# trackoon_solar.net
KiCad netlist of a schematic drawn in EAGLE
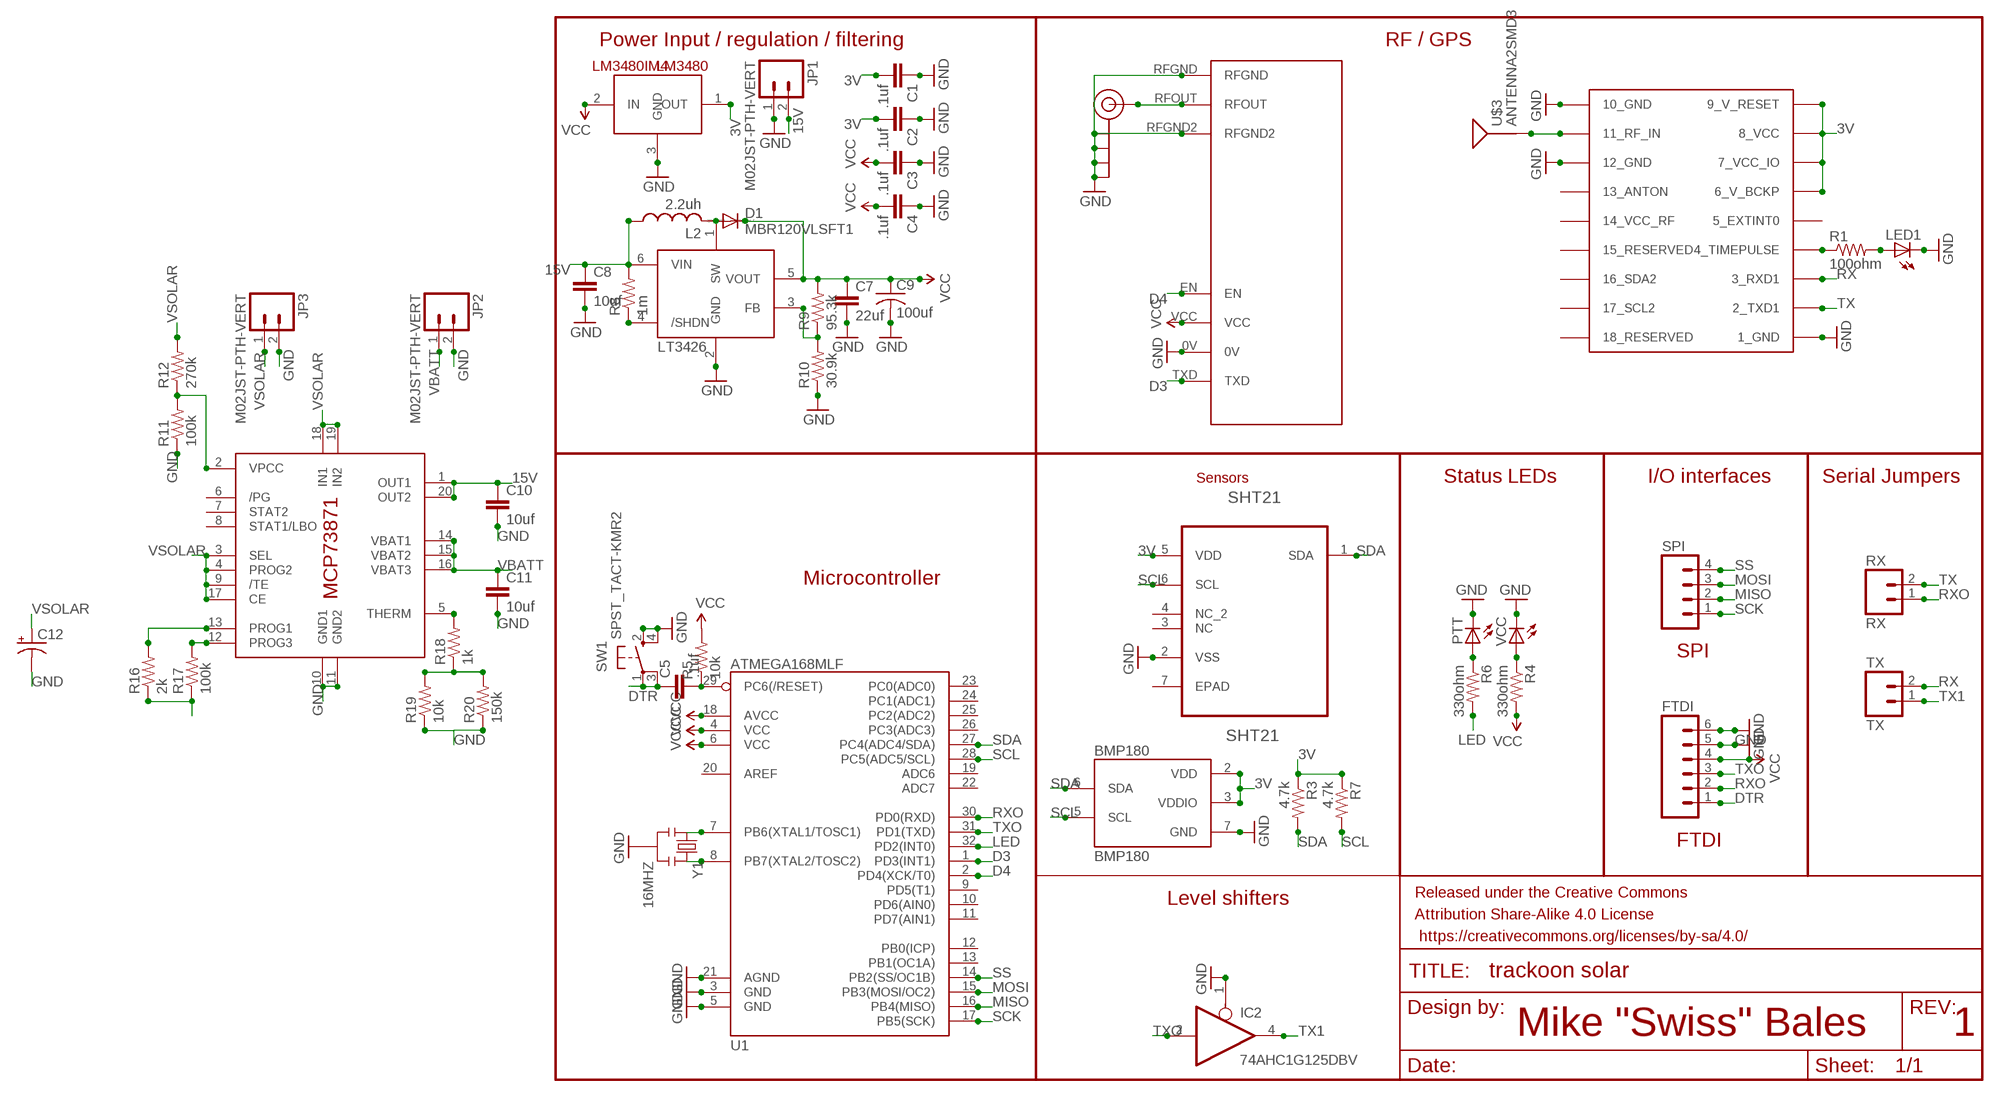
[diagram p0: schematic, sheet 1]

(export (version "E")
  (design (tool "Eeschema 10.0.6"))
  (components
    (comp (ref "BMP180")
      (value "BMP180")
      (footprint "eagle-import:BMP180")
      (libsource (lib "eagle-import") (part "BMP180"))
    )
    (comp (ref "C1")
      (value ".1uf")
      (footprint "eagle-import:0805")
      (libsource (lib "eagle-import") (part "CAP0805"))
    )
    (comp (ref "C2")
      (value ".1uf")
      (footprint "eagle-import:0805")
      (libsource (lib "eagle-import") (part "CAP0805"))
    )
    (comp (ref "C3")
      (value ".1uf")
      (footprint "eagle-import:0805")
      (libsource (lib "eagle-import") (part "CAP0805"))
    )
    (comp (ref "C4")
      (value ".1uf")
      (footprint "eagle-import:0805")
      (libsource (lib "eagle-import") (part "CAP0805"))
    )
    (comp (ref "C5")
      (value ".1uf")
      (footprint "eagle-import:0805")
      (libsource (lib "eagle-import") (part "CAP0805"))
    )
    (comp (ref "C7")
      (value "22uf")
      (footprint "eagle-import:0805")
      (libsource (lib "eagle-import") (part "CAP0805"))
    )
    (comp (ref "C8")
      (value "10uf")
      (footprint "eagle-import:0805")
      (libsource (lib "eagle-import") (part "CAP0805"))
    )
    (comp (ref "C9")
      (value "100uf")
      (footprint "eagle-import:C1206")
      (libsource (lib "eagle-import") (part "C-USC1206"))
    )
    (comp (ref "C10")
      (value "10uf")
      (footprint "eagle-import:0805")
      (libsource (lib "eagle-import") (part "CAP0805"))
    )
    (comp (ref "C11")
      (value "10uf")
      (footprint "eagle-import:0805")
      (libsource (lib "eagle-import") (part "CAP0805"))
    )
    (comp (ref "C12")
      (value "CPOL-US153CLV-1012")
      (footprint "eagle-import:153CLV-1012")
      (libsource (lib "eagle-import") (part "CPOL-US153CLV-1012"))
    )
    (comp (ref "D1")
      (value "MBR120VLSFT1")
      (footprint "eagle-import:SOD123")
      (libsource (lib "eagle-import") (part "DIODE-SOD123"))
    )
    (comp (ref "FRAME1")
      (value "FRAME-LETTER")
      (footprint "eagle-import:CREATIVE_COMMONS")
      (libsource (lib "eagle-import") (part "FRAME-LETTER"))
    )
    (comp (ref "FTDI")
      (value "M06NO_SILK_FEMALE_PTH")
      (footprint "eagle-import:1X06_NO_SILK")
      (libsource (lib "eagle-import") (part "M06NO_SILK_FEMALE_PTH"))
    )
    (comp (ref "IC1")
      (value "MCP73871")
      (footprint "eagle-import:QFN20")
      (libsource (lib "eagle-import") (part "MCP73871"))
    )
    (comp (ref "IC2")
      (value "74AHC1G125DBV")
      (footprint "eagle-import:SOT23-5")
      (libsource (lib "eagle-import") (part "741G125DBVAHC"))
    )
    (comp (ref "J$1")
      (value "SMA_EDGE")
      (footprint "eagle-import:SMA-EDGE")
      (libsource (lib "eagle-import") (part "SMA_EDGE"))
    )
    (comp (ref "JP1")
      (value "M02JST-PTH-VERT")
      (footprint "eagle-import:JST-2-PTH-VERT")
      (libsource (lib "eagle-import") (part "M02JST-PTH-VERT"))
    )
    (comp (ref "JP2")
      (value "M02JST-PTH-VERT")
      (footprint "eagle-import:JST-2-PTH-VERT")
      (libsource (lib "eagle-import") (part "M02JST-PTH-VERT"))
    )
    (comp (ref "JP3")
      (value "M02JST-PTH-VERT")
      (footprint "eagle-import:JST-2-PTH-VERT")
      (libsource (lib "eagle-import") (part "M02JST-PTH-VERT"))
    )
    (comp (ref "L2")
      (value "2.2uh")
      (footprint "eagle-import:L1812")
      (libsource (lib "eagle-import") (part "L-USL1812"))
    )
    (comp (ref "LED1")
      (value "LEDCHIP-LED0805")
      (footprint "eagle-import:CHIP-LED0805")
      (libsource (lib "eagle-import") (part "LEDCHIP-LED0805"))
    )
    (comp (ref "LM3480")
      (value "LM3480IM4")
      (footprint "eagle-import:SOT23-3")
      (libsource (lib "eagle-import") (part "LM3480IM4"))
    )
    (comp (ref "LT3426")
      (value "LT3426")
      (footprint "eagle-import:SOT23-6")
      (libsource (lib "eagle-import") (part "LT3426"))
    )
    (comp (ref "PTT")
      (value "LEDCHIP-LED0805")
      (footprint "eagle-import:CHIP-LED0805")
      (libsource (lib "eagle-import") (part "LEDCHIP-LED0805"))
    )
    (comp (ref "R1")
      (value "100ohm")
      (footprint "eagle-import:0805")
      (libsource (lib "eagle-import") (part "RESISTOR0805-RES"))
    )
    (comp (ref "R3")
      (value "4.7k")
      (footprint "eagle-import:0805")
      (libsource (lib "eagle-import") (part "RESISTOR0805-RES"))
    )
    (comp (ref "R4")
      (value "330ohm")
      (footprint "eagle-import:0805")
      (libsource (lib "eagle-import") (part "RESISTOR0805-RES"))
    )
    (comp (ref "R5")
      (value "10k")
      (footprint "eagle-import:0805")
      (libsource (lib "eagle-import") (part "RESISTOR0805-RES"))
    )
    (comp (ref "R6")
      (value "330ohm")
      (footprint "eagle-import:0805")
      (libsource (lib "eagle-import") (part "RESISTOR0805-RES"))
    )
    (comp (ref "R7")
      (value "4.7k")
      (footprint "eagle-import:0805")
      (libsource (lib "eagle-import") (part "RESISTOR0805-RES"))
    )
    (comp (ref "R8")
      (value "1m")
      (footprint "eagle-import:0805")
      (libsource (lib "eagle-import") (part "RESISTOR0805-RES"))
    )
    (comp (ref "R9")
      (value "95.3k")
      (footprint "eagle-import:0805")
      (libsource (lib "eagle-import") (part "RESISTOR0805-RES"))
    )
    (comp (ref "R10")
      (value "30.9k")
      (footprint "eagle-import:0805")
      (libsource (lib "eagle-import") (part "RESISTOR0805-RES"))
    )
    (comp (ref "R11")
      (value "100k")
      (footprint "eagle-import:0805")
      (libsource (lib "eagle-import") (part "RESISTOR0805-RES"))
    )
    (comp (ref "R12")
      (value "270k")
      (footprint "eagle-import:0805")
      (libsource (lib "eagle-import") (part "RESISTOR0805-RES"))
    )
    (comp (ref "R16")
      (value "2k")
      (footprint "eagle-import:0805")
      (libsource (lib "eagle-import") (part "RESISTOR0805-RES"))
    )
    (comp (ref "R17")
      (value "100k")
      (footprint "eagle-import:0805")
      (libsource (lib "eagle-import") (part "RESISTOR0805-RES"))
    )
    (comp (ref "R18")
      (value "1k")
      (footprint "eagle-import:0805")
      (libsource (lib "eagle-import") (part "RESISTOR0805-RES"))
    )
    (comp (ref "R19")
      (value "10k")
      (footprint "eagle-import:0805")
      (libsource (lib "eagle-import") (part "RESISTOR0805-RES"))
    )
    (comp (ref "R20")
      (value "150k")
      (footprint "eagle-import:0805")
      (libsource (lib "eagle-import") (part "RESISTOR0805-RES"))
    )
    (comp (ref "RX")
      (value "RX")
      (footprint "eagle-import:1X02")
      (libsource (lib "eagle-import") (part "M02PTH"))
    )
    (comp (ref "SHT21")
      (value "SHT21")
      (footprint "eagle-import:DFN300X300X110-7N")
      (libsource (lib "eagle-import") (part "SHT21"))
    )
    (comp (ref "SPI")
      (value "M041X04_NO_SILK")
      (footprint "eagle-import:1X04_NO_SILK")
      (libsource (lib "eagle-import") (part "M041X04_NO_SILK"))
    )
    (comp (ref "SW1")
      (value "SPST_TACT-KMR2")
      (footprint "eagle-import:KMR2")
      (libsource (lib "eagle-import") (part "SPST_TACT-KMR2"))
    )
    (comp (ref "TX")
      (value "TX")
      (footprint "eagle-import:1X02")
      (libsource (lib "eagle-import") (part "M02PTH"))
    )
    (comp (ref "U$1")
      (value "UBLOX_MAX")
      (footprint "eagle-import:UBLOX_MAX")
      (libsource (lib "eagle-import") (part "UBLOX_MAX"))
    )
    (comp (ref "U$2")
      (value "RADIOMETRIX-HX1")
      (footprint "eagle-import:RADIOMETRIX-HX1")
      (libsource (lib "eagle-import") (part "RADIOMETRIX-HX1"))
    )
    (comp (ref "U$3")
      (value "ANTENNA2SMD3")
      (footprint "eagle-import:ANTENNA-CHIP4")
      (libsource (lib "eagle-import") (part "ANTENNA2SMD3"))
    )
    (comp (ref "U1")
      (value "ATMEGA168MLF")
      (footprint "eagle-import:MLF32")
      (libsource (lib "eagle-import") (part "ATMEGA168MLF"))
    )
    (comp (ref "VCC")
      (value "LEDCHIP-LED0805")
      (footprint "eagle-import:CHIP-LED0805")
      (libsource (lib "eagle-import") (part "LEDCHIP-LED0805"))
    )
    (comp (ref "Y1")
      (value "16MHZ")
      (footprint "eagle-import:RESONATOR-SMD")
      (libsource (lib "eagle-import") (part "RESONATOR16MHZ"))
    )
  )
  (nets
    (net (code "1") (name "/3V") (class "Default")
      (node (ref "BMP180") (pin "2") (pinfunction "VDD_2") (pintype "power_in"))
      (node (ref "BMP180") (pin "3") (pinfunction "VDDIO_3") (pintype "power_in"))
      (node (ref "C1") (pin "2") (pinfunction "2_2") (pintype "passive"))
      (node (ref "C2") (pin "2") (pinfunction "2_2") (pintype "passive"))
      (node (ref "LM3480") (pin "1") (pinfunction "OUT_1") (pintype "bidirectional"))
      (node (ref "R3") (pin "1") (pinfunction "1_1") (pintype "passive"))
      (node (ref "R7") (pin "1") (pinfunction "1_1") (pintype "passive"))
      (node (ref "SHT21") (pin "5") (pinfunction "VDD_5") (pintype "power_in"))
      (node (ref "U$1") (pin "6_V_BCKP") (pinfunction "6_V_BCKP_6_V_BCKP") (pintype "bidirectional"))
      (node (ref "U$1") (pin "7_VCC_IO") (pinfunction "7_VCC_IO_7_VCC_IO") (pintype "power_in"))
      (node (ref "U$1") (pin "8_VCC") (pinfunction "8_VCC_8_VCC") (pintype "power_in"))
      (node (ref "U$1") (pin "9_V_RESET") (pinfunction "9_V_RESET_9_V_RESET") (pintype "power_in"))
    )
    (net (code "2") (name "/15V") (class "Default")
      (node (ref "C10") (pin "1") (pinfunction "1_1") (pintype "passive"))
      (node (ref "C8") (pin "1") (pinfunction "1_1") (pintype "passive"))
      (node (ref "IC1") (pin "1") (pinfunction "OUT1_1") (pintype "output"))
      (node (ref "IC1") (pin "20") (pinfunction "OUT2_20") (pintype "output"))
      (node (ref "JP1") (pin "2") (pinfunction "2_2") (pintype "passive"))
      (node (ref "L2") (pin "1") (pinfunction "1_1") (pintype "passive"))
      (node (ref "LT3426") (pin "6") (pinfunction "VIN_6") (pintype "input"))
      (node (ref "R8") (pin "2") (pinfunction "2_2") (pintype "passive"))
    )
    (net (code "3") (name "/D3") (class "Default")
      (node (ref "U$2") (pin "TXD") (pinfunction "TXD_TXD") (pintype "bidirectional"))
      (node (ref "U1") (pin "1") (pinfunction "PD3(INT1)_1") (pintype "bidirectional"))
    )
    (net (code "4") (name "/D4") (class "Default")
      (node (ref "U$2") (pin "EN") (pinfunction "EN_EN") (pintype "bidirectional"))
      (node (ref "U1") (pin "2") (pinfunction "PD4(XCK/T0)_2") (pintype "bidirectional"))
    )
    (net (code "5") (name "/DTR") (class "Default")
      (node (ref "C5") (pin "1") (pinfunction "1_1") (pintype "passive"))
      (node (ref "FTDI") (pin "1") (pinfunction "1_1") (pintype "passive"))
      (node (ref "SW1") (pin "1") (pinfunction "P_1") (pintype "passive"))
      (node (ref "SW1") (pin "3") (pinfunction "P1_3") (pintype "passive"))
    )
    (net (code "6") (name "/LED") (class "Default")
      (node (ref "R6") (pin "2") (pinfunction "2_2") (pintype "passive"))
      (node (ref "U1") (pin "32") (pinfunction "PD2(INT0)_32") (pintype "bidirectional"))
    )
    (net (code "7") (name "/MISO") (class "Default")
      (node (ref "SPI") (pin "2") (pinfunction "2_2") (pintype "passive"))
      (node (ref "U1") (pin "16") (pinfunction "PB4(MISO)_16") (pintype "bidirectional"))
    )
    (net (code "8") (name "/MOSI") (class "Default")
      (node (ref "SPI") (pin "3") (pinfunction "3_3") (pintype "passive"))
      (node (ref "U1") (pin "15") (pinfunction "PB3(MOSI/OC2)_15") (pintype "bidirectional"))
    )
    (net (code "9") (name "/RX") (class "Default")
      (node (ref "TX") (pin "2") (pinfunction "2_2") (pintype "passive"))
      (node (ref "U$1") (pin "3_RXD1") (pinfunction "3_RXD1_3_RXD1") (pintype "bidirectional"))
    )
    (net (code "10") (name "/RXO") (class "Default")
      (node (ref "FTDI") (pin "2") (pinfunction "2_2") (pintype "passive"))
      (node (ref "RX") (pin "1") (pinfunction "1_1") (pintype "passive"))
      (node (ref "U1") (pin "30") (pinfunction "PD0(RXD)_30") (pintype "bidirectional"))
    )
    (net (code "11") (name "/SCK") (class "Default")
      (node (ref "SPI") (pin "1") (pinfunction "1_1") (pintype "passive"))
      (node (ref "U1") (pin "17") (pinfunction "PB5(SCK)_17") (pintype "bidirectional"))
    )
    (net (code "12") (name "/SCL") (class "Default")
      (node (ref "BMP180") (pin "5") (pinfunction "SCL_5") (pintype "input"))
      (node (ref "R7") (pin "2") (pinfunction "2_2") (pintype "passive"))
      (node (ref "SHT21") (pin "6") (pinfunction "SCL_6") (pintype "input"))
      (node (ref "U1") (pin "28") (pinfunction "PC5(ADC5/SCL)_28") (pintype "bidirectional"))
    )
    (net (code "13") (name "/SDA") (class "Default")
      (node (ref "BMP180") (pin "6") (pinfunction "SDA_6") (pintype "bidirectional"))
      (node (ref "R3") (pin "2") (pinfunction "2_2") (pintype "passive"))
      (node (ref "SHT21") (pin "1") (pinfunction "SDA_1") (pintype "bidirectional"))
      (node (ref "U1") (pin "27") (pinfunction "PC4(ADC4/SDA)_27") (pintype "bidirectional"))
    )
    (net (code "14") (name "/SS") (class "Default")
      (node (ref "SPI") (pin "4") (pinfunction "4_4") (pintype "passive"))
      (node (ref "U1") (pin "14") (pinfunction "PB2(SS/OC1B)_14") (pintype "bidirectional"))
    )
    (net (code "15") (name "/TX") (class "Default")
      (node (ref "RX") (pin "2") (pinfunction "2_2") (pintype "passive"))
      (node (ref "U$1") (pin "2_TXD1") (pinfunction "2_TXD1_2_TXD1") (pintype "bidirectional"))
    )
    (net (code "16") (name "/TX1") (class "Default")
      (node (ref "IC2") (pin "4") (pinfunction "O_4") (pintype "tri_state"))
      (node (ref "TX") (pin "1") (pinfunction "1_1") (pintype "passive"))
    )
    (net (code "17") (name "/TXO") (class "Default")
      (node (ref "FTDI") (pin "3") (pinfunction "3_3") (pintype "passive"))
      (node (ref "IC2") (pin "2") (pinfunction "I_2") (pintype "input"))
      (node (ref "U1") (pin "31") (pinfunction "PD1(TXD)_31") (pintype "bidirectional"))
    )
    (net (code "18") (name "/VBATT") (class "Default")
      (node (ref "C11") (pin "1") (pinfunction "1_1") (pintype "passive"))
      (node (ref "IC1") (pin "14") (pinfunction "VBAT1_14") (pintype "output"))
      (node (ref "IC1") (pin "15") (pinfunction "VBAT2_15") (pintype "output"))
      (node (ref "IC1") (pin "16") (pinfunction "VBAT3_16") (pintype "output"))
      (node (ref "JP2") (pin "1") (pinfunction "1_1") (pintype "passive"))
    )
    (net (code "19") (name "/VSOLAR") (class "Default")
      (node (ref "C12") (pin "+") (pinfunction "+_+") (pintype "passive"))
      (node (ref "IC1") (pin "17") (pinfunction "CE_17") (pintype "input"))
      (node (ref "IC1") (pin "18") (pinfunction "IN1_18") (pintype "input"))
      (node (ref "IC1") (pin "19") (pinfunction "IN2_19") (pintype "input"))
      (node (ref "IC1") (pin "3") (pinfunction "SEL_3") (pintype "input"))
      (node (ref "IC1") (pin "4") (pinfunction "PROG2_4") (pintype "input"))
      (node (ref "IC1") (pin "9") (pinfunction "/TE_9") (pintype "input"))
      (node (ref "JP3") (pin "1") (pinfunction "1_1") (pintype "passive"))
      (node (ref "R12") (pin "2") (pinfunction "2_2") (pintype "passive"))
    )
    (net (code "20") (name "GND") (class "Default")
      (node (ref "BMP180") (pin "7") (pinfunction "GND_7") (pintype "power_in"))
      (node (ref "C1") (pin "1") (pinfunction "1_1") (pintype "passive"))
      (node (ref "C10") (pin "2") (pinfunction "2_2") (pintype "passive"))
      (node (ref "C11") (pin "2") (pinfunction "2_2") (pintype "passive"))
      (node (ref "C12") (pin "-") (pinfunction "-_-") (pintype "passive"))
      (node (ref "C2") (pin "1") (pinfunction "1_1") (pintype "passive"))
      (node (ref "C3") (pin "1") (pinfunction "1_1") (pintype "passive"))
      (node (ref "C4") (pin "1") (pinfunction "1_1") (pintype "passive"))
      (node (ref "C7") (pin "2") (pinfunction "2_2") (pintype "passive"))
      (node (ref "C8") (pin "2") (pinfunction "2_2") (pintype "passive"))
      (node (ref "C9") (pin "2") (pinfunction "2_2") (pintype "passive"))
      (node (ref "FTDI") (pin "5") (pinfunction "5_5") (pintype "passive"))
      (node (ref "FTDI") (pin "6") (pinfunction "6_6") (pintype "passive"))
      (node (ref "IC1") (pin "10") (pinfunction "GND1_10") (pintype "power_in"))
      (node (ref "IC1") (pin "11") (pinfunction "GND2_11") (pintype "power_in"))
      (node (ref "IC2") (pin "1") (pinfunction "OE_1") (pintype "input"))
      (node (ref "J$1") (pin "GND@0") (pinfunction "GND_GND@0") (pintype "bidirectional"))
      (node (ref "J$1") (pin "GND@1") (pinfunction "GND_GND@1") (pintype "bidirectional"))
      (node (ref "J$1") (pin "GND@2") (pinfunction "GND_GND@2") (pintype "bidirectional"))
      (node (ref "J$1") (pin "GND@3") (pinfunction "GND_GND@3") (pintype "bidirectional"))
      (node (ref "JP1") (pin "1") (pinfunction "1_1") (pintype "passive"))
      (node (ref "JP2") (pin "2") (pinfunction "2_2") (pintype "passive"))
      (node (ref "JP3") (pin "2") (pinfunction "2_2") (pintype "passive"))
      (node (ref "LED1") (pin "C") (pinfunction "C_C") (pintype "passive"))
      (node (ref "LM3480") (pin "3") (pinfunction "GND_3") (pintype "bidirectional"))
      (node (ref "LT3426") (pin "2") (pinfunction "GND_2") (pintype "power_in"))
      (node (ref "PTT") (pin "C") (pinfunction "C_C") (pintype "passive"))
      (node (ref "R10") (pin "1") (pinfunction "1_1") (pintype "passive"))
      (node (ref "R11") (pin "1") (pinfunction "1_1") (pintype "passive"))
      (node (ref "R16") (pin "1") (pinfunction "1_1") (pintype "passive"))
      (node (ref "R17") (pin "1") (pinfunction "1_1") (pintype "passive"))
      (node (ref "R19") (pin "1") (pinfunction "1_1") (pintype "passive"))
      (node (ref "R20") (pin "1") (pinfunction "1_1") (pintype "passive"))
      (node (ref "SHT21") (pin "2") (pinfunction "VSS_2") (pintype "power_in"))
      (node (ref "SW1") (pin "2") (pinfunction "S_2") (pintype "passive"))
      (node (ref "SW1") (pin "4") (pinfunction "S1_4") (pintype "passive"))
      (node (ref "U$1") (pin "10_GND") (pinfunction "10_GND_10_GND") (pintype "power_in"))
      (node (ref "U$1") (pin "12_GND") (pinfunction "12_GND_12_GND") (pintype "power_in"))
      (node (ref "U$1") (pin "1_GND") (pinfunction "1_GND_1_GND") (pintype "power_in"))
      (node (ref "U$2") (pin "0V") (pinfunction "0V_0V") (pintype "bidirectional"))
      (node (ref "U$2") (pin "RFGND") (pinfunction "RFGND_RFGND") (pintype "bidirectional"))
      (node (ref "U$2") (pin "RFGND2") (pinfunction "RFGND2_RFGND2") (pintype "bidirectional"))
      (node (ref "U1") (pin "21") (pinfunction "AGND_21") (pintype "bidirectional"))
      (node (ref "U1") (pin "3") (pinfunction "GND_3") (pintype "bidirectional"))
      (node (ref "U1") (pin "5") (pinfunction "GND_5") (pintype "bidirectional"))
      (node (ref "VCC") (pin "C") (pinfunction "C_C") (pintype "passive"))
      (node (ref "Y1") (pin "2") (pinfunction "2_2") (pintype "passive"))
    )
    (net (code "21") (name "Net-(IC1-PROG1)") (class "Default")
      (node (ref "IC1") (pin "13") (pinfunction "PROG1_13") (pintype "input"))
      (node (ref "R16") (pin "2") (pinfunction "2_2") (pintype "passive"))
    )
    (net (code "22") (name "Net-(IC1-PROG3)") (class "Default")
      (node (ref "IC1") (pin "12") (pinfunction "PROG3_12") (pintype "input"))
      (node (ref "R17") (pin "2") (pinfunction "2_2") (pintype "passive"))
    )
    (net (code "23") (name "Net-(IC1-THERM)") (class "Default")
      (node (ref "IC1") (pin "5") (pinfunction "THERM_5") (pintype "input"))
      (node (ref "R18") (pin "2") (pinfunction "2_2") (pintype "passive"))
    )
    (net (code "24") (name "Net-(IC1-VPCC)") (class "Default")
      (node (ref "IC1") (pin "2") (pinfunction "VPCC_2") (pintype "input"))
      (node (ref "R11") (pin "2") (pinfunction "2_2") (pintype "passive"))
      (node (ref "R12") (pin "1") (pinfunction "1_1") (pintype "passive"))
    )
    (net (code "25") (name "Net-(J$1-SIGNAL)") (class "Default")
      (node (ref "J$1") (pin "SIG") (pinfunction "SIGNAL_SIG") (pintype "bidirectional"))
      (node (ref "U$2") (pin "RFOUT") (pinfunction "RFOUT_RFOUT") (pintype "bidirectional"))
    )
    (net (code "26") (name "Net-(LED1-PadA)") (class "Default")
      (node (ref "LED1") (pin "A") (pinfunction "A_A") (pintype "passive"))
      (node (ref "R1") (pin "2") (pinfunction "2_2") (pintype "passive"))
    )
    (net (code "27") (name "Net-(LT3426-FB)") (class "Default")
      (node (ref "LT3426") (pin "3") (pinfunction "FB_3") (pintype "input"))
      (node (ref "R10") (pin "2") (pinfunction "2_2") (pintype "passive"))
      (node (ref "R9") (pin "1") (pinfunction "1_1") (pintype "passive"))
    )
    (net (code "28") (name "Net-(LT3426-SW)") (class "Default")
      (node (ref "D1") (pin "A") (pinfunction "A_A") (pintype "passive"))
      (node (ref "L2") (pin "2") (pinfunction "2_2") (pintype "passive"))
      (node (ref "LT3426") (pin "1") (pinfunction "SW_1") (pintype "output"))
    )
    (net (code "29") (name "Net-(LT3426-{slash}SHDN)") (class "Default")
      (node (ref "LT3426") (pin "4") (pinfunction "/SHDN_4") (pintype "input"))
      (node (ref "R8") (pin "1") (pinfunction "1_1") (pintype "passive"))
    )
    (net (code "30") (name "Net-(PTT-PadA)") (class "Default")
      (node (ref "PTT") (pin "A") (pinfunction "A_A") (pintype "passive"))
      (node (ref "R6") (pin "1") (pinfunction "1_1") (pintype "passive"))
    )
    (net (code "31") (name "Net-(R1-Pad1)") (class "Default")
      (node (ref "R1") (pin "1") (pinfunction "1_1") (pintype "passive"))
      (node (ref "U$1") (pin "4_TIMEPULSE") (pinfunction "4_TIMEPULSE_4_TIMEPULSE") (pintype "bidirectional"))
    )
    (net (code "32") (name "Net-(R4-Pad1)") (class "Default")
      (node (ref "R4") (pin "1") (pinfunction "1_1") (pintype "passive"))
      (node (ref "VCC") (pin "A") (pinfunction "A_A") (pintype "passive"))
    )
    (net (code "33") (name "Net-(R18-Pad1)") (class "Default")
      (node (ref "R18") (pin "1") (pinfunction "1_1") (pintype "passive"))
      (node (ref "R19") (pin "2") (pinfunction "2_2") (pintype "passive"))
      (node (ref "R20") (pin "2") (pinfunction "2_2") (pintype "passive"))
    )
    (net (code "34") (name "Net-(U$3-SIGNAL)") (class "Default")
      (node (ref "U$1") (pin "11_RF_IN") (pinfunction "11_RF_IN_11_RF_IN") (pintype "bidirectional"))
      (node (ref "U$3") (pin "SIG") (pinfunction "SIGNAL_SIG") (pintype "bidirectional"))
    )
    (net (code "35") (name "Net-(U1-PB6(XTAL1{slash}TOSC1))") (class "Default")
      (node (ref "U1") (pin "7") (pinfunction "PB6(XTAL1/TOSC1)_7") (pintype "bidirectional"))
      (node (ref "Y1") (pin "1") (pinfunction "1_1") (pintype "passive"))
    )
    (net (code "36") (name "Net-(U1-PB7(XTAL2{slash}TOSC2))") (class "Default")
      (node (ref "U1") (pin "8") (pinfunction "PB7(XTAL2/TOSC2)_8") (pintype "bidirectional"))
      (node (ref "Y1") (pin "3") (pinfunction "3_3") (pintype "passive"))
    )
    (net (code "37") (name "Net-(U1-PC6({slash}RESET))") (class "Default")
      (node (ref "C5") (pin "2") (pinfunction "2_2") (pintype "passive"))
      (node (ref "R5") (pin "1") (pinfunction "1_1") (pintype "passive"))
      (node (ref "U1") (pin "29") (pinfunction "PC6(/RESET)_29") (pintype "bidirectional"))
    )
    (net (code "38") (name "VCC") (class "Default")
      (node (ref "C3") (pin "2") (pinfunction "2_2") (pintype "passive"))
      (node (ref "C4") (pin "2") (pinfunction "2_2") (pintype "passive"))
      (node (ref "C7") (pin "1") (pinfunction "1_1") (pintype "passive"))
      (node (ref "C9") (pin "1") (pinfunction "1_1") (pintype "passive"))
      (node (ref "D1") (pin "C") (pinfunction "C_C") (pintype "passive"))
      (node (ref "FTDI") (pin "4") (pinfunction "4_4") (pintype "passive"))
      (node (ref "LM3480") (pin "2") (pinfunction "IN_2") (pintype "bidirectional"))
      (node (ref "LT3426") (pin "5") (pinfunction "VOUT_5") (pintype "output"))
      (node (ref "R4") (pin "2") (pinfunction "2_2") (pintype "passive"))
      (node (ref "R5") (pin "2") (pinfunction "2_2") (pintype "passive"))
      (node (ref "R9") (pin "2") (pinfunction "2_2") (pintype "passive"))
      (node (ref "U$2") (pin "VCC") (pinfunction "VCC_VCC") (pintype "bidirectional"))
      (node (ref "U1") (pin "18") (pinfunction "AVCC_18") (pintype "bidirectional"))
      (node (ref "U1") (pin "4") (pinfunction "VCC_4") (pintype "bidirectional"))
      (node (ref "U1") (pin "6") (pinfunction "VCC_6") (pintype "bidirectional"))
    )
    (net (code "39") (name "unconnected-(IC1-STAT1{slash}LBO-Pad8)") (class "Default")
      (node (ref "IC1") (pin "8") (pinfunction "STAT1/LBO_8") (pintype "output"))
    )
    (net (code "40") (name "unconnected-(IC1-STAT2-Pad7)") (class "Default")
      (node (ref "IC1") (pin "7") (pinfunction "STAT2_7") (pintype "output"))
    )
    (net (code "41") (name "unconnected-(IC1-{slash}PG-Pad6)") (class "Default")
      (node (ref "IC1") (pin "6") (pinfunction "/PG_6") (pintype "output"))
    )
    (net (code "42") (name "unconnected-(SHT21-EPAD-Pad7)") (class "Default")
      (node (ref "SHT21") (pin "7") (pinfunction "EPAD_7") (pintype "passive"))
    )
    (net (code "43") (name "unconnected-(SHT21-NC-Pad3)") (class "Default")
      (node (ref "SHT21") (pin "3") (pinfunction "NC_3") (pintype "no_connect"))
    )
    (net (code "44") (name "unconnected-(SHT21-NC_2-Pad4)") (class "Default")
      (node (ref "SHT21") (pin "4") (pinfunction "NC_2_4") (pintype "no_connect"))
    )
    (net (code "45") (name "unconnected-(U$1-Pad5_EXTINT0)") (class "Default")
      (node (ref "U$1") (pin "5_EXTINT0") (pinfunction "5_EXTINT0_5_EXTINT0") (pintype "bidirectional"))
    )
    (net (code "46") (name "unconnected-(U$1-Pad13_ANTON)") (class "Default")
      (node (ref "U$1") (pin "13_ANTON") (pinfunction "13_ANTON_13_ANTON") (pintype "bidirectional"))
    )
    (net (code "47") (name "unconnected-(U$1-Pad14_VCC_RF)") (class "Default")
      (node (ref "U$1") (pin "14_VCC_RF") (pinfunction "14_VCC_RF_14_VCC_RF") (pintype "bidirectional"))
    )
    (net (code "48") (name "unconnected-(U$1-Pad15_RESERVED)") (class "Default")
      (node (ref "U$1") (pin "15_RESERVED") (pinfunction "15_RESERVED_15_RESERVED") (pintype "bidirectional"))
    )
    (net (code "49") (name "unconnected-(U$1-Pad16_SDA2)") (class "Default")
      (node (ref "U$1") (pin "16_SDA2") (pinfunction "16_SDA2_16_SDA2") (pintype "bidirectional"))
    )
    (net (code "50") (name "unconnected-(U$1-Pad17_SCL2)") (class "Default")
      (node (ref "U$1") (pin "17_SCL2") (pinfunction "17_SCL2_17_SCL2") (pintype "bidirectional"))
    )
    (net (code "51") (name "unconnected-(U$1-Pad18_RESERVED)") (class "Default")
      (node (ref "U$1") (pin "18_RESERVED") (pinfunction "18_RESERVED_18_RESERVED") (pintype "bidirectional"))
    )
    (net (code "52") (name "unconnected-(U1-ADC6-Pad19)") (class "Default")
      (node (ref "U1") (pin "19") (pinfunction "ADC6_19") (pintype "bidirectional"))
    )
    (net (code "53") (name "unconnected-(U1-ADC7-Pad22)") (class "Default")
      (node (ref "U1") (pin "22") (pinfunction "ADC7_22") (pintype "bidirectional"))
    )
    (net (code "54") (name "unconnected-(U1-AREF-Pad20)") (class "Default")
      (node (ref "U1") (pin "20") (pinfunction "AREF_20") (pintype "bidirectional"))
    )
    (net (code "55") (name "unconnected-(U1-PB0(ICP)-Pad12)") (class "Default")
      (node (ref "U1") (pin "12") (pinfunction "PB0(ICP)_12") (pintype "bidirectional"))
    )
    (net (code "56") (name "unconnected-(U1-PB1(OC1A)-Pad13)") (class "Default")
      (node (ref "U1") (pin "13") (pinfunction "PB1(OC1A)_13") (pintype "bidirectional"))
    )
    (net (code "57") (name "unconnected-(U1-PC0(ADC0)-Pad23)") (class "Default")
      (node (ref "U1") (pin "23") (pinfunction "PC0(ADC0)_23") (pintype "bidirectional"))
    )
    (net (code "58") (name "unconnected-(U1-PC1(ADC1)-Pad24)") (class "Default")
      (node (ref "U1") (pin "24") (pinfunction "PC1(ADC1)_24") (pintype "bidirectional"))
    )
    (net (code "59") (name "unconnected-(U1-PC2(ADC2)-Pad25)") (class "Default")
      (node (ref "U1") (pin "25") (pinfunction "PC2(ADC2)_25") (pintype "bidirectional"))
    )
    (net (code "60") (name "unconnected-(U1-PC3(ADC3)-Pad26)") (class "Default")
      (node (ref "U1") (pin "26") (pinfunction "PC3(ADC3)_26") (pintype "bidirectional"))
    )
    (net (code "61") (name "unconnected-(U1-PD5(T1)-Pad9)") (class "Default")
      (node (ref "U1") (pin "9") (pinfunction "PD5(T1)_9") (pintype "bidirectional"))
    )
    (net (code "62") (name "unconnected-(U1-PD6(AIN0)-Pad10)") (class "Default")
      (node (ref "U1") (pin "10") (pinfunction "PD6(AIN0)_10") (pintype "bidirectional"))
    )
    (net (code "63") (name "unconnected-(U1-PD7(AIN1)-Pad11)") (class "Default")
      (node (ref "U1") (pin "11") (pinfunction "PD7(AIN1)_11") (pintype "bidirectional"))
    )
  )
)
